# supply.net
KiCad netlist of a schematic drawn in Altium Designer
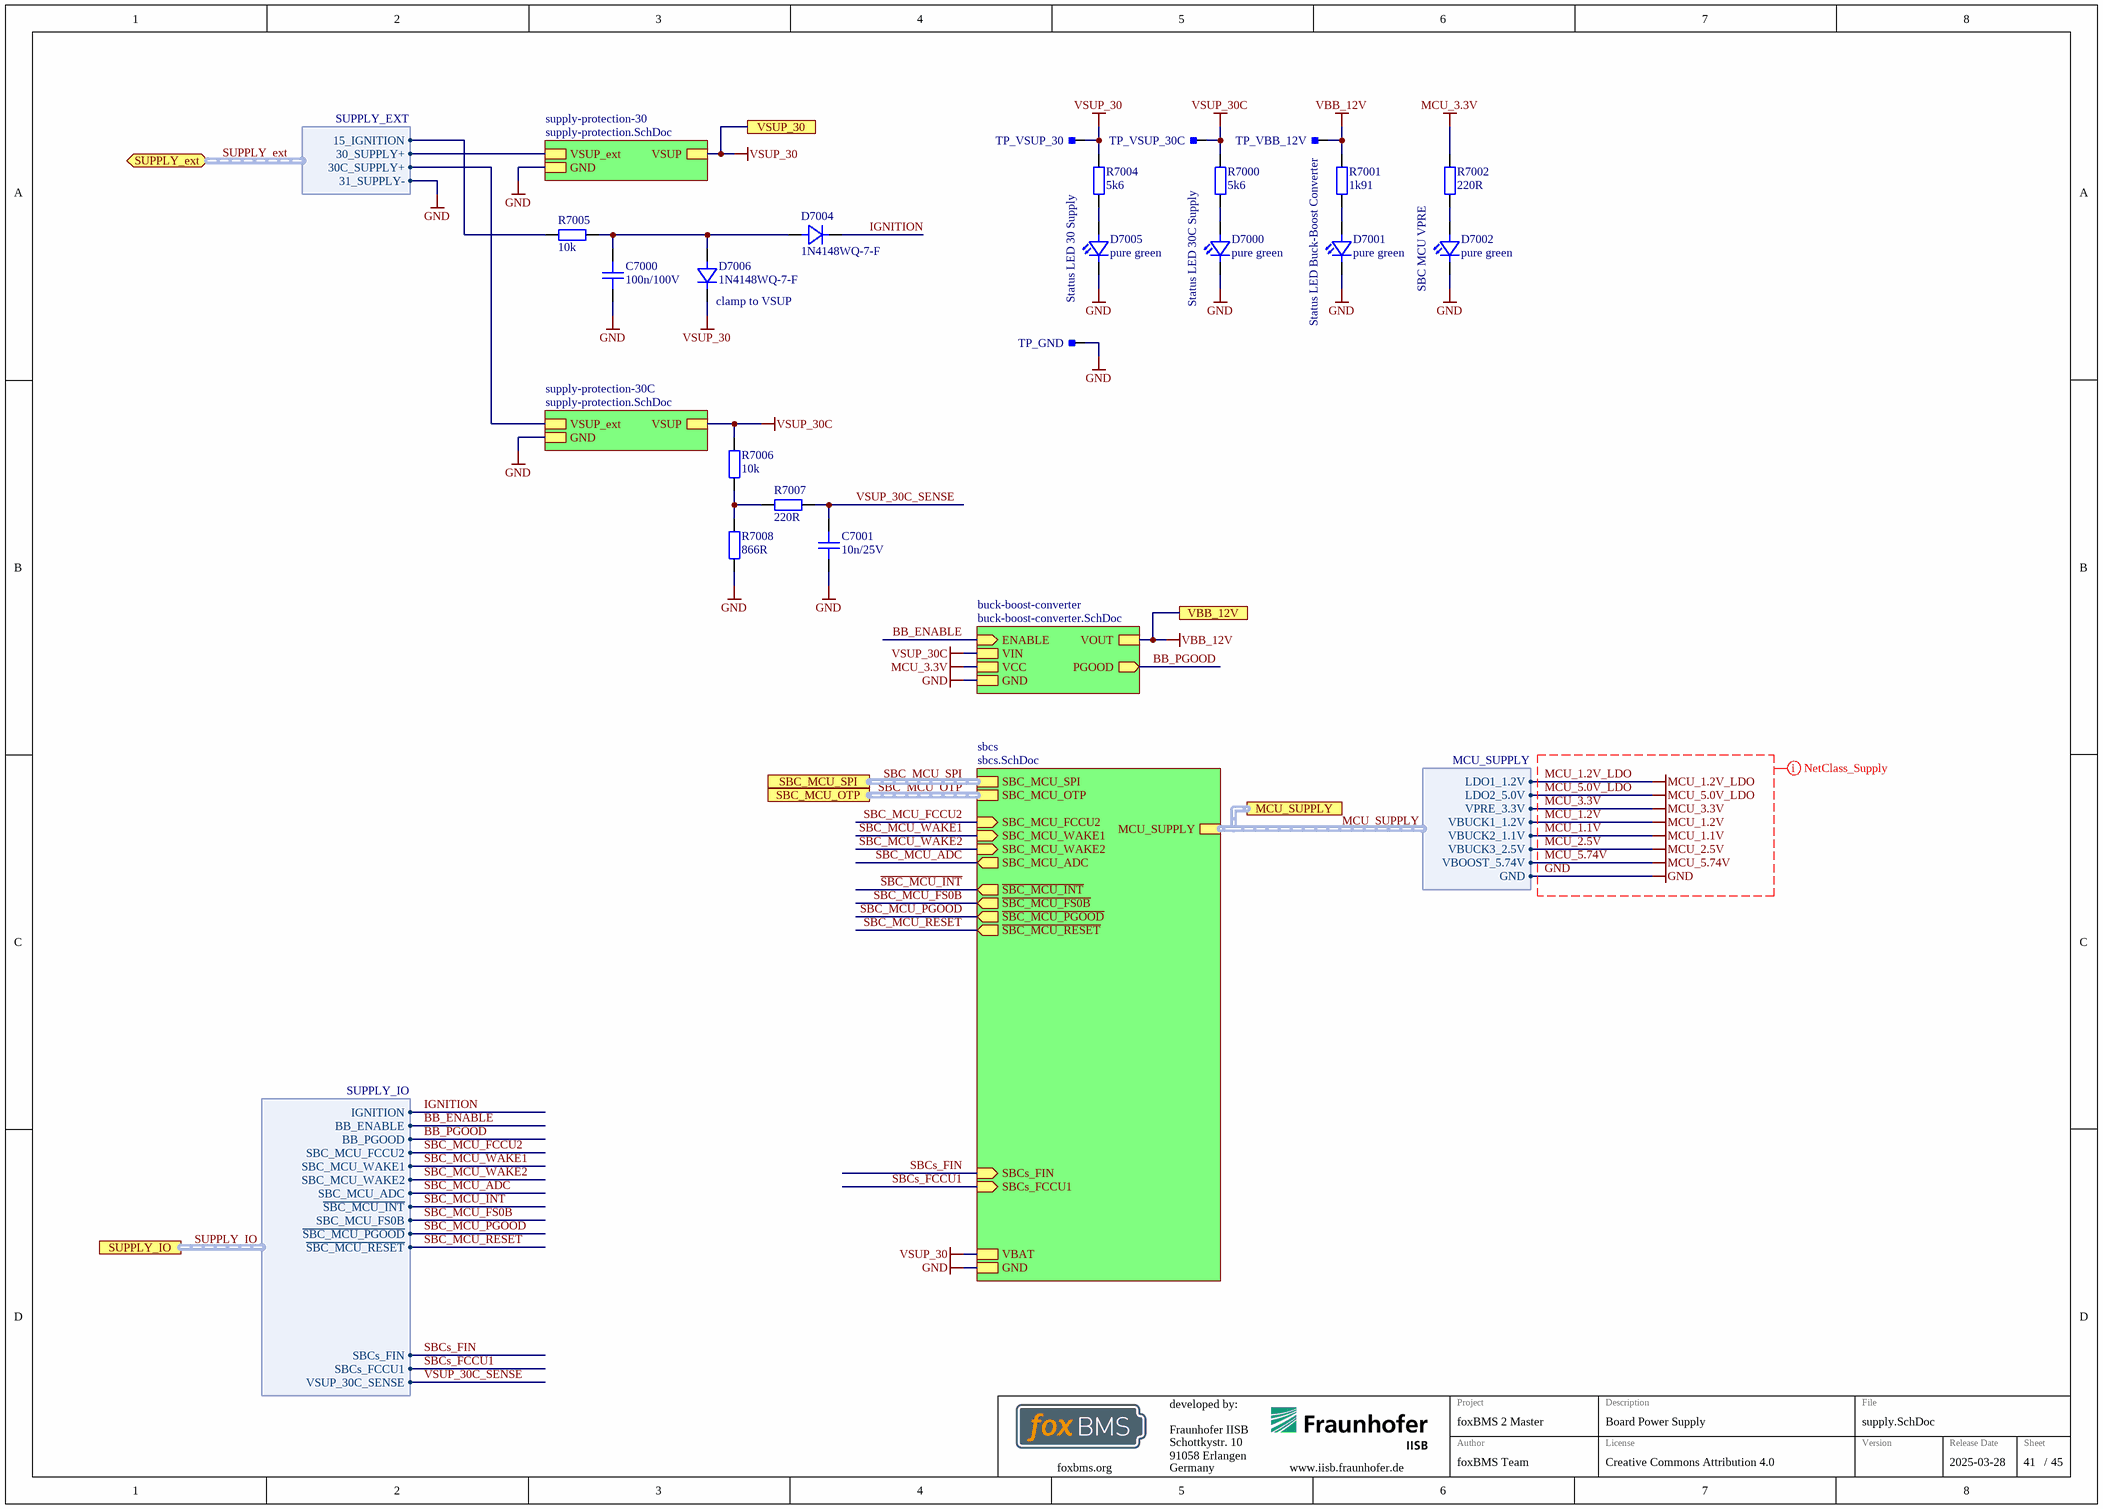
[diagram p0: supply.SchDoc]

(export (version "E")
  (design (tool "Eeschema 10.0.6"))
  (components
    (comp (ref "C7000")
      (value "100n/100V")
      (footprint "CAPC1608X08N")
      (description "MLCC")
      (fields (field (name "PART NUMBER") "gen_C_ceramic_100n_100V_X7R_0603"))
      (libsource (lib "OE750") (part "C"))
    )
    (comp (ref "C7001")
      (value "10n/25V")
      (footprint "CAPC1005X06N")
      (description "MLCC")
      (fields (field (name "PART NUMBER") "gen_C_ceramic_10n_25V_X7R_0402"))
      (libsource (lib "OE750") (part "C"))
    )
    (comp (ref "D7000")
      (value "pure green")
      (footprint "LEDC1608X07N")
      (description "TLMP1100-GS08")
      (fields (field (name "PART NUMBER") "LED_0603_pure_green_AECQ") (field (name "MANUFACTURER") "Vishay"))
      (libsource (lib "OE750") (part "D_LED"))
    )
    (comp (ref "D7001")
      (value "pure green")
      (footprint "LEDC1608X07N")
      (description "TLMP1100-GS08")
      (fields (field (name "PART NUMBER") "LED_0603_pure_green_AECQ") (field (name "MANUFACTURER") "Vishay"))
      (libsource (lib "OE750") (part "D_LED"))
    )
    (comp (ref "D7002")
      (value "pure green")
      (footprint "LEDC1608X07N")
      (description "TLMP1100-GS08")
      (fields (field (name "PART NUMBER") "LED_0603_pure_green_AECQ") (field (name "MANUFACTURER") "Vishay"))
      (libsource (lib "OE750") (part "D_LED"))
    )
    (comp (ref "D7004")
      (value "1N4148WQ-7-F")
      (footprint "SOD-123_CASE-425-04-ISSUE-G")
      (description "Diode")
      (fields (field (name "MANUFACTURER") "Diodes Inc."))
      (libsource (lib "OE750") (part "D"))
    )
    (comp (ref "D7005")
      (value "pure green")
      (footprint "LEDC1608X07N")
      (description "TLMP1100-GS08")
      (fields (field (name "PART NUMBER") "LED_0603_pure_green_AECQ") (field (name "MANUFACTURER") "Vishay"))
      (libsource (lib "OE750") (part "D_LED"))
    )
    (comp (ref "D7006")
      (value "1N4148WQ-7-F")
      (footprint "SOD-123_CASE-425-04-ISSUE-G")
      (description "Diode")
      (fields (field (name "MANUFACTURER") "Diodes Inc."))
      (libsource (lib "OE750") (part "D"))
    )
    (comp (ref "R7000")
      (value "5k6")
      (footprint "RESC1005X04N")
      (description "SMD Resistor 5k6 0402")
      (fields (field (name "PART NUMBER") "gen_R_5k6_0402") (field (name "TOLERANCE") "1%"))
      (libsource (lib "OE750") (part "R"))
    )
    (comp (ref "R7001")
      (value "1k91")
      (footprint "RESC1005X04N")
      (description "SMD Resistor 1k91 0402")
      (fields (field (name "PART NUMBER") "gen_R_1k91_0402") (field (name "TOLERANCE") "1%"))
      (libsource (lib "OE750") (part "R"))
    )
    (comp (ref "R7002")
      (value "220R")
      (footprint "RESC1005X04N")
      (description "SMD Resistor 220R 0402")
      (fields (field (name "PART NUMBER") "gen_R_220R_0402") (field (name "TOLERANCE") "1%"))
      (libsource (lib "OE750") (part "R"))
    )
    (comp (ref "R7004")
      (value "5k6")
      (footprint "RESC1005X04N")
      (description "SMD Resistor 5k6 0402")
      (fields (field (name "PART NUMBER") "gen_R_5k6_0402") (field (name "TOLERANCE") "1%"))
      (libsource (lib "OE750") (part "R"))
    )
    (comp (ref "R7005")
      (value "10k")
      (footprint "RESC1005X04N")
      (description "SMD Resistor 10k 0402")
      (fields (field (name "PART NUMBER") "gen_R_10k_0402") (field (name "TOLERANCE") "1%"))
      (libsource (lib "OE750") (part "R"))
    )
    (comp (ref "R7006")
      (value "10k")
      (footprint "RESC1005X04N")
      (description "SMD Resistor 10k 0402")
      (fields (field (name "PART NUMBER") "gen_R_10k_0402") (field (name "TOLERANCE") "1%"))
      (libsource (lib "OE750") (part "R"))
    )
    (comp (ref "R7007")
      (value "220R")
      (footprint "RESC1005X04N")
      (description "SMD Resistor 220R 0402")
      (fields (field (name "PART NUMBER") "gen_R_220R_0402") (field (name "TOLERANCE") "1%"))
      (libsource (lib "OE750") (part "R"))
    )
    (comp (ref "R7008")
      (value "866R")
      (footprint "RESC1005X04N")
      (description "SMD Resistor 866R 0402")
      (fields (field (name "PART NUMBER") "gen_R_866R_0402") (field (name "TOLERANCE") "1%"))
      (libsource (lib "OE750") (part "R"))
    )
    (comp (ref "TP_GND")
      (value "Testpoint_Square")
      (footprint "Testpoint_S1")
      (description "Testpoint, square")
      (libsource (lib "OE750") (part "Testpoint_Square"))
    )
    (comp (ref "TP_VBB_12V")
      (value "Testpoint_Square")
      (footprint "Testpoint_S1")
      (description "Testpoint, square")
      (libsource (lib "OE750") (part "Testpoint_Square"))
    )
    (comp (ref "TP_VSUP_30")
      (value "Testpoint_Square")
      (footprint "Testpoint_S1")
      (description "Testpoint, square")
      (libsource (lib "OE750") (part "Testpoint_Square"))
    )
    (comp (ref "TP_VSUP_30C")
      (value "Testpoint_Square")
      (footprint "Testpoint_S1")
      (description "Testpoint, square")
      (libsource (lib "OE750") (part "Testpoint_Square"))
    )
  )
  (nets
    (net (code "6") (name "/15_IGNITION") (class "Default")
      (node (ref "R7005") (pin "2") (pinfunction "2_2") (pintype "passive"))
    )
    (net (code "11") (name "/IGNITION") (class "Default")
      (node (ref "D7004") (pin "1") (pinfunction "K_1") (pintype "passive"))
    )
    (net (code "25") (name "/VSUP_30C_SENSE") (class "Default")
      (node (ref "C7001") (pin "2") (pinfunction "2_2") (pintype "passive"))
      (node (ref "R7007") (pin "2") (pinfunction "2_2") (pintype "passive"))
    )
    (net (code "28") (name "GND") (class "Default")
      (node (ref "C7000") (pin "1") (pinfunction "1_1") (pintype "passive"))
      (node (ref "C7001") (pin "1") (pinfunction "1_1") (pintype "passive"))
      (node (ref "D7000") (pin "1") (pinfunction "C_1") (pintype "passive"))
      (node (ref "D7001") (pin "1") (pinfunction "C_1") (pintype "passive"))
      (node (ref "D7002") (pin "1") (pinfunction "C_1") (pintype "passive"))
      (node (ref "D7005") (pin "1") (pinfunction "C_1") (pintype "passive"))
      (node (ref "R7008") (pin "1") (pinfunction "1_1") (pintype "passive"))
      (node (ref "TP_GND") (pin "1") (pinfunction "1_1") (pintype "passive"))
    )
    (net (code "33") (name "MCU_3.3V") (class "Default")
      (node (ref "R7002") (pin "2") (pinfunction "2_2") (pintype "passive"))
    )
    (net (code "36") (name "Net-(D7000-A)") (class "Default")
      (node (ref "D7000") (pin "2") (pinfunction "A_2") (pintype "passive"))
      (node (ref "R7000") (pin "1") (pinfunction "1_1") (pintype "passive"))
    )
    (net (code "37") (name "Net-(D7001-A)") (class "Default")
      (node (ref "D7001") (pin "2") (pinfunction "A_2") (pintype "passive"))
      (node (ref "R7001") (pin "1") (pinfunction "1_1") (pintype "passive"))
    )
    (net (code "38") (name "Net-(D7002-A)") (class "Default")
      (node (ref "D7002") (pin "2") (pinfunction "A_2") (pintype "passive"))
      (node (ref "R7002") (pin "1") (pinfunction "1_1") (pintype "passive"))
    )
    (net (code "39") (name "Net-(D7004-A)") (class "Default")
      (node (ref "C7000") (pin "2") (pinfunction "2_2") (pintype "passive"))
      (node (ref "D7004") (pin "2") (pinfunction "A_2") (pintype "passive"))
      (node (ref "D7006") (pin "2") (pinfunction "A_2") (pintype "passive"))
      (node (ref "R7005") (pin "1") (pinfunction "1_1") (pintype "passive"))
    )
    (net (code "40") (name "Net-(D7005-A)") (class "Default")
      (node (ref "D7005") (pin "2") (pinfunction "A_2") (pintype "passive"))
      (node (ref "R7004") (pin "1") (pinfunction "1_1") (pintype "passive"))
    )
    (net (code "41") (name "Net-(R7006-Pad1)") (class "Default")
      (node (ref "R7006") (pin "1") (pinfunction "1_1") (pintype "passive"))
      (node (ref "R7007") (pin "1") (pinfunction "1_1") (pintype "passive"))
      (node (ref "R7008") (pin "2") (pinfunction "2_2") (pintype "passive"))
    )
    (net (code "42") (name "VBB_12V") (class "Default")
      (node (ref "R7001") (pin "2") (pinfunction "2_2") (pintype "passive"))
      (node (ref "TP_VBB_12V") (pin "1") (pinfunction "1_1") (pintype "passive"))
    )
    (net (code "43") (name "VSUP_30") (class "Default")
      (node (ref "D7006") (pin "1") (pinfunction "K_1") (pintype "passive"))
      (node (ref "R7004") (pin "2") (pinfunction "2_2") (pintype "passive"))
      (node (ref "TP_VSUP_30") (pin "1") (pinfunction "1_1") (pintype "passive"))
    )
    (net (code "44") (name "VSUP_30C") (class "Default")
      (node (ref "R7000") (pin "2") (pinfunction "2_2") (pintype "passive"))
      (node (ref "R7006") (pin "2") (pinfunction "2_2") (pintype "passive"))
      (node (ref "TP_VSUP_30C") (pin "1") (pinfunction "1_1") (pintype "passive"))
    )
  )
)
